# Input.net
KiCad netlist of a schematic drawn in Altium Designer
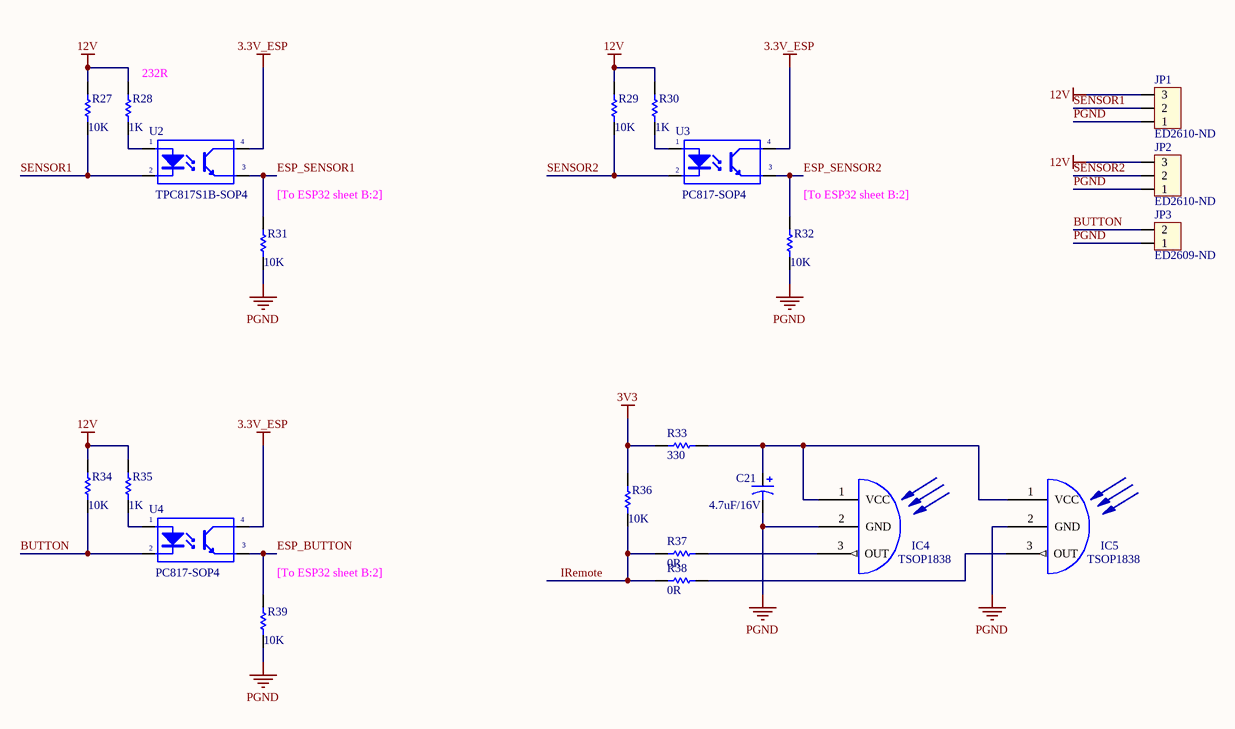
[diagram p0: Input.SchDoc]

(export (version "E")
  (design (tool "Eeschema 10.0.6"))
  (components
    (comp (ref "C21")
      (value "4.7uF/16V")
      (footprint "C0805")
      (description "Polarized Capacitor (Radial)")
      (fields (field (name "Comment") "Cap Pol1") (field (name "PUBLISHER") "Altium Limited"))
      (libsource (lib "Miscellaneous Devices") (part "Cap Pol1"))
    )
    (comp (ref "IC4")
      (value "TSOP1838")
      (footprint "TSOP1838")
      (libsource (lib "Tran Tuan") (part "TSOP1838"))
    )
    (comp (ref "IC5")
      (value "TSOP1838")
      (footprint "TSOP1838")
      (libsource (lib "Tran Tuan") (part "TSOP1838"))
    )
    (comp (ref "JP1")
      (value "ED2610-ND")
      (footprint "DOMINO_OSTTC_3P")
      (description "3 Position Wire to Board Terminal Block Horizontal with Board 0.200\" (5.08mm) Through Hole")
      (libsource (lib "lpson") (part "Con3"))
    )
    (comp (ref "JP2")
      (value "ED2610-ND")
      (footprint "DOMINO_OSTTC_3P")
      (description "3 Position Wire to Board Terminal Block Horizontal with Board 0.200\" (5.08mm) Through Hole")
      (libsource (lib "lpson") (part "Con3"))
    )
    (comp (ref "JP3")
      (value "ED2609-ND")
      (footprint "DOMINO_OSTTC_2P")
      (description "2 Position Wire to Board Terminal Block Horizontal with Board 0.200\" (5.08mm) Through Hole")
      (libsource (lib "lpson") (part "Con2"))
    )
    (comp (ref "R27")
      (value "10K")
      (footprint "Res 0805 SMD")
      (description "RES SMD 10K OHM 1% 1/10W 0603")
      (fields
        (field (name "MANUFACTURER") "Yageo")
        (field (name "MANUFACTURER PART NUMBER") "RC0603FR-0710KL")
      )
      (libsource (lib "GSHT_181013") (part "10K/R0603/1%"))
    )
    (comp (ref "R28")
      (value "1K")
      (footprint "Res 0805 SMD")
      (description "1 kOhms ±1% 0.125W, 1/8W Chip Resistor 0805 (2012 Metric) Automotive AEC-Q200 Thick Film")
      (libsource (lib "GSHT_181013") (part "10K/R0603/1%"))
    )
    (comp (ref "R29")
      (value "10K")
      (footprint "Res 0805 SMD")
      (description "RES SMD 10K OHM 1% 1/10W 0603")
      (fields
        (field (name "MANUFACTURER") "Yageo")
        (field (name "MANUFACTURER PART NUMBER") "RC0603FR-0710KL")
      )
      (libsource (lib "GSHT_181013") (part "10K/R0603/1%"))
    )
    (comp (ref "R30")
      (value "1K")
      (footprint "Res 0805 SMD")
      (description "1 kOhms ±1% 0.125W, 1/8W Chip Resistor 0805 (2012 Metric) Automotive AEC-Q200 Thick Film")
      (libsource (lib "GSHT_181013") (part "10K/R0603/1%"))
    )
    (comp (ref "R31")
      (value "10K")
      (footprint "Res 0805 SMD")
      (description "RES SMD 249K OHM 1% 1/10W 0805")
      (fields
        (field (name "MANUFACTURER") "Yageo")
        (field (name "MANUFACTURER PART NUMBER") "RC0603FR-07249KL")
      )
      (libsource (lib "GSHT_181013") (part "249K/R0805/1%"))
    )
    (comp (ref "R32")
      (value "10K")
      (footprint "Res 0805 SMD")
      (description "RES SMD 249K OHM 1% 1/10W 0805")
      (fields
        (field (name "MANUFACTURER") "Yageo")
        (field (name "MANUFACTURER PART NUMBER") "RC0603FR-07249KL")
      )
      (libsource (lib "GSHT_181013") (part "249K/R0805/1%"))
    )
    (comp (ref "R33")
      (value "330")
      (footprint "Res 0805 SMD")
      (description "RES SMD 249K OHM 1% 1/10W 0805")
      (fields
        (field (name "MANUFACTURER") "Yageo")
        (field (name "MANUFACTURER PART NUMBER") "RC0603FR-07249KL")
      )
      (libsource (lib "GSHT_181013") (part "249K/R0805/1%"))
    )
    (comp (ref "R34")
      (value "10K")
      (footprint "Res 0805 SMD")
      (description "RES SMD 10K OHM 1% 1/10W 0603")
      (fields
        (field (name "MANUFACTURER") "Yageo")
        (field (name "MANUFACTURER PART NUMBER") "RC0603FR-0710KL")
      )
      (libsource (lib "GSHT_181013") (part "10K/R0603/1%"))
    )
    (comp (ref "R35")
      (value "1K")
      (footprint "Res 0805 SMD")
      (description "1 kOhms ±1% 0.125W, 1/8W Chip Resistor 0805 (2012 Metric) Automotive AEC-Q200 Thick Film")
      (libsource (lib "GSHT_181013") (part "10K/R0603/1%"))
    )
    (comp (ref "R36")
      (value "10K")
      (footprint "Res 0805 SMD")
      (description "RES SMD 249K OHM 1% 1/10W 0805")
      (fields
        (field (name "MANUFACTURER") "Yageo")
        (field (name "MANUFACTURER PART NUMBER") "RC0603FR-07249KL")
      )
      (libsource (lib "GSHT_181013") (part "249K/R0805/1%"))
    )
    (comp (ref "R37")
      (value "0R")
      (footprint "Res 0805 SMD")
      (description "RES SMD 249K OHM 1% 1/10W 0805")
      (fields
        (field (name "MANUFACTURER") "Yageo")
        (field (name "MANUFACTURER PART NUMBER") "RC0603FR-07249KL")
      )
      (libsource (lib "GSHT_181013") (part "249K/R0805/1%"))
    )
    (comp (ref "R38")
      (value "0R")
      (footprint "Res 0805 SMD")
      (description "RES SMD 249K OHM 1% 1/10W 0805")
      (fields
        (field (name "MANUFACTURER") "Yageo")
        (field (name "MANUFACTURER PART NUMBER") "RC0603FR-07249KL")
      )
      (libsource (lib "GSHT_181013") (part "249K/R0805/1%"))
    )
    (comp (ref "R39")
      (value "10K")
      (footprint "Res 0805 SMD")
      (description "RES SMD 249K OHM 1% 1/10W 0805")
      (fields
        (field (name "MANUFACTURER") "Yageo")
        (field (name "MANUFACTURER PART NUMBER") "RC0603FR-07249KL")
      )
      (libsource (lib "GSHT_181013") (part "249K/R0805/1%"))
    )
    (comp (ref "U2")
      (value "TPC817S1B-SOP4")
      (footprint "TPC817-4SOP")
      (description "Optoisolator Transistor Output 5000Vrms 1 Channel 4-SOP")
      (libsource (lib "lpson") (part "PC817"))
    )
    (comp (ref "U3")
      (value "PC817-SOP4")
      (footprint "TPC817-4SOP")
      (description "Optoisolator Transistor Output 5000Vrms 1 Channel 4-SOP")
      (libsource (lib "lpson") (part "PC817"))
    )
    (comp (ref "U4")
      (value "PC817-SOP4")
      (footprint "TPC817-4SOP")
      (description "Optoisolator Transistor Output 5000Vrms 1 Channel 4-SOP")
      (libsource (lib "lpson") (part "PC817"))
    )
  )
  (nets
    (net (code "1") (name "/BUTTON") (class "Default")
      (node (ref "JP3") (pin "2") (pinfunction "2_2") (pintype "passive"))
      (node (ref "R34") (pin "1") (pinfunction "1_1") (pintype "passive"))
      (node (ref "U4") (pin "2") (pinfunction "K_2") (pintype "passive"))
    )
    (net (code "2") (name "/ESP_BUTTON") (class "Default")
      (node (ref "R39") (pin "2") (pinfunction "2_2") (pintype "passive"))
      (node (ref "U4") (pin "3") (pinfunction "E_3") (pintype "passive"))
    )
    (net (code "3") (name "/ESP_SENSOR1") (class "Default")
      (node (ref "R31") (pin "2") (pinfunction "2_2") (pintype "passive"))
      (node (ref "U2") (pin "3") (pinfunction "E_3") (pintype "passive"))
    )
    (net (code "4") (name "/ESP_SENSOR2") (class "Default")
      (node (ref "R32") (pin "2") (pinfunction "2_2") (pintype "passive"))
      (node (ref "U3") (pin "3") (pinfunction "E_3") (pintype "passive"))
    )
    (net (code "5") (name "/IRemote") (class "Default")
      (node (ref "R36") (pin "1") (pinfunction "1_1") (pintype "passive"))
      (node (ref "R37") (pin "2") (pinfunction "2_2") (pintype "passive"))
      (node (ref "R38") (pin "2") (pinfunction "2_2") (pintype "passive"))
    )
    (net (code "6") (name "/SENSOR1") (class "Default")
      (node (ref "JP1") (pin "2") (pinfunction "2_2") (pintype "passive"))
      (node (ref "R27") (pin "1") (pinfunction "1_1") (pintype "passive"))
      (node (ref "U2") (pin "2") (pinfunction "K_2") (pintype "passive"))
    )
    (net (code "7") (name "/SENSOR2") (class "Default")
      (node (ref "JP2") (pin "2") (pinfunction "2_2") (pintype "passive"))
      (node (ref "R29") (pin "1") (pinfunction "1_1") (pintype "passive"))
      (node (ref "U3") (pin "2") (pinfunction "K_2") (pintype "passive"))
    )
    (net (code "8") (name "3.3V_ESP") (class "Default")
      (node (ref "U2") (pin "4") (pinfunction "C_4") (pintype "passive"))
      (node (ref "U3") (pin "4") (pinfunction "C_4") (pintype "passive"))
      (node (ref "U4") (pin "4") (pinfunction "C_4") (pintype "passive"))
    )
    (net (code "9") (name "3V3") (class "Default")
      (node (ref "R33") (pin "2") (pinfunction "2_2") (pintype "passive"))
      (node (ref "R36") (pin "2") (pinfunction "2_2") (pintype "passive"))
    )
    (net (code "10") (name "12V") (class "Default")
      (node (ref "JP1") (pin "3") (pinfunction "3_3") (pintype "passive"))
      (node (ref "JP2") (pin "3") (pinfunction "3_3") (pintype "passive"))
      (node (ref "R27") (pin "2") (pinfunction "2_2") (pintype "passive"))
      (node (ref "R28") (pin "2") (pinfunction "2_2") (pintype "passive"))
      (node (ref "R29") (pin "2") (pinfunction "2_2") (pintype "passive"))
      (node (ref "R30") (pin "2") (pinfunction "2_2") (pintype "passive"))
      (node (ref "R34") (pin "2") (pinfunction "2_2") (pintype "passive"))
      (node (ref "R35") (pin "2") (pinfunction "2_2") (pintype "passive"))
    )
    (net (code "11") (name "Net-(IC4-OUT)") (class "Default")
      (node (ref "IC4") (pin "3") (pinfunction "OUT_3") (pintype "output"))
      (node (ref "R37") (pin "1") (pinfunction "1_1") (pintype "passive"))
    )
    (net (code "12") (name "Net-(IC4-VCC)") (class "Default")
      (node (ref "C21") (pin "1") (pinfunction "1_1") (pintype "passive"))
      (node (ref "IC4") (pin "1") (pinfunction "VCC_1") (pintype "power_in"))
      (node (ref "IC5") (pin "1") (pinfunction "VCC_1") (pintype "power_in"))
      (node (ref "R33") (pin "1") (pinfunction "1_1") (pintype "passive"))
    )
    (net (code "13") (name "Net-(IC5-OUT)") (class "Default")
      (node (ref "IC5") (pin "3") (pinfunction "OUT_3") (pintype "output"))
      (node (ref "R38") (pin "1") (pinfunction "1_1") (pintype "passive"))
    )
    (net (code "14") (name "Net-(U2-A)") (class "Default")
      (node (ref "R28") (pin "1") (pinfunction "1_1") (pintype "passive"))
      (node (ref "U2") (pin "1") (pinfunction "A_1") (pintype "passive"))
    )
    (net (code "15") (name "Net-(U3-A)") (class "Default")
      (node (ref "R30") (pin "1") (pinfunction "1_1") (pintype "passive"))
      (node (ref "U3") (pin "1") (pinfunction "A_1") (pintype "passive"))
    )
    (net (code "16") (name "Net-(U4-A)") (class "Default")
      (node (ref "R35") (pin "1") (pinfunction "1_1") (pintype "passive"))
      (node (ref "U4") (pin "1") (pinfunction "A_1") (pintype "passive"))
    )
    (net (code "17") (name "PGND") (class "Default")
      (node (ref "C21") (pin "2") (pinfunction "2_2") (pintype "passive"))
      (node (ref "IC4") (pin "2") (pinfunction "GND_2") (pintype "power_in"))
      (node (ref "IC5") (pin "2") (pinfunction "GND_2") (pintype "power_in"))
      (node (ref "JP1") (pin "1") (pinfunction "1_1") (pintype "passive"))
      (node (ref "JP2") (pin "1") (pinfunction "1_1") (pintype "passive"))
      (node (ref "JP3") (pin "1") (pinfunction "1_1") (pintype "passive"))
      (node (ref "R31") (pin "1") (pinfunction "1_1") (pintype "passive"))
      (node (ref "R32") (pin "1") (pinfunction "1_1") (pintype "passive"))
      (node (ref "R39") (pin "1") (pinfunction "1_1") (pintype "passive"))
    )
  )
)
